# USB_RS485_Conv.net
KiCad netlist of a schematic drawn in EAGLE
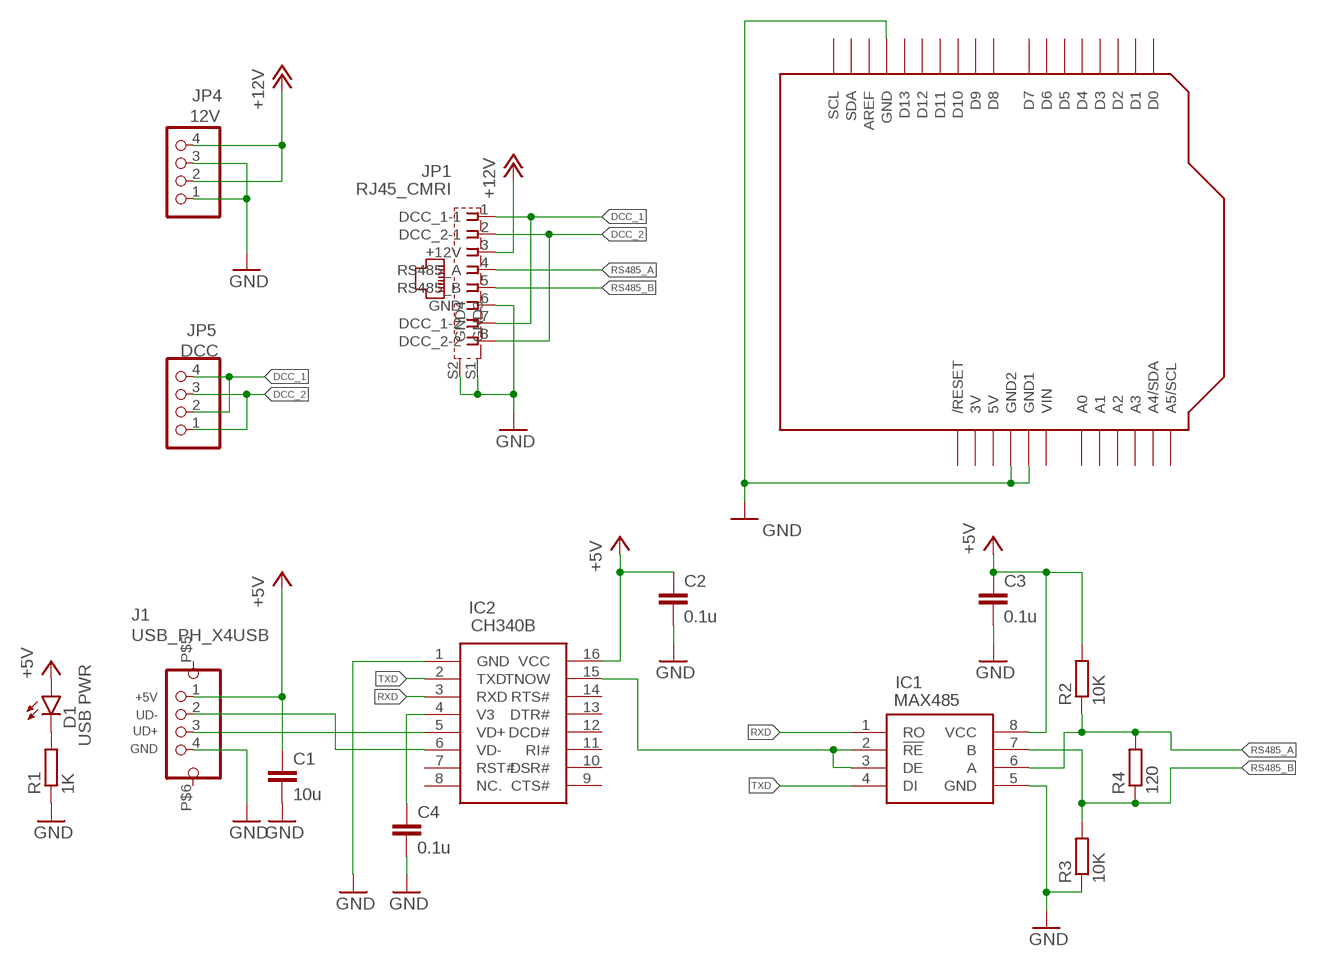
[diagram p0: schematic, sheet 1]

(export (version "E")
  (design (tool "Eeschema 10.0.6"))
  (components
    (comp (ref "C1")
      (value "10u")
      (footprint "eagle-import:C1206")
      (libsource (lib "eagle-import") (part "C-EUC1206"))
    )
    (comp (ref "C2")
      (value "0.1u")
      (footprint "eagle-import:C1206")
      (libsource (lib "eagle-import") (part "C-EUC1206"))
    )
    (comp (ref "C3")
      (value "0.1u")
      (footprint "eagle-import:C1206")
      (libsource (lib "eagle-import") (part "C-EUC1206"))
    )
    (comp (ref "C4")
      (value "0.1u")
      (footprint "eagle-import:C1206")
      (libsource (lib "eagle-import") (part "C-EUC1206"))
    )
    (comp (ref "D1")
      (value "USB PWR")
      (footprint "eagle-import:LED_SMD_1608")
      (libsource (lib "eagle-import") (part "LEDSMD_1608"))
    )
    (comp (ref "IC1")
      (value "MAX485")
      (footprint "eagle-import:SOIC127P600X175-8N")
      (fields (field (name "MANUFACTURER_PART_NUMBER") "MAX485CSA") (field (name "RS_PART_NUMBER") "0370854"))
      (libsource (lib "eagle-import") (part "MAX485CSA"))
    )
    (comp (ref "IC2")
      (value "CH340B")
      (footprint "eagle-import:SOIC127P600X177-16N")
      (fields (field (name "MANUFACTURER_PART_NUMBER") "ULN2003A-DIP16"))
      (libsource (lib "eagle-import") (part "CH340B"))
    )
    (comp (ref "J1")
      (value "USB_PH_X4USB")
      (footprint "eagle-import:USB_PH_04_90")
      (libsource (lib "eagle-import") (part "USB_PH_X4USB"))
    )
    (comp (ref "JP1")
      (value "RJ45_CMRI")
      (footprint "eagle-import:RJ45_7810")
      (libsource (lib "eagle-import") (part "RJ45_CMRI"))
    )
    (comp (ref "JP4")
      (value "12V")
      (footprint "eagle-import:1X04_90")
      (libsource (lib "eagle-import") (part "PINHD-1X4/90"))
    )
    (comp (ref "JP5")
      (value "DCC")
      (footprint "eagle-import:1X04_90")
      (libsource (lib "eagle-import") (part "PINHD-1X4/90"))
    )
    (comp (ref "Q1")
      (value "ARDUINO-SHIELD-NOTEXT")
      (footprint "eagle-import:ARDUINO-SHIELD")
      (libsource (lib "eagle-import") (part "ARDUINO-SHIELD-NOTEXT"))
    )
    (comp (ref "R1")
      (value "1K")
      (footprint "eagle-import:R1206")
      (libsource (lib "eagle-import") (part "R-EU_R1206"))
    )
    (comp (ref "R2")
      (value "10K")
      (footprint "eagle-import:R1206")
      (libsource (lib "eagle-import") (part "R-EU_R1206"))
    )
    (comp (ref "R3")
      (value "10K")
      (footprint "eagle-import:R1206")
      (libsource (lib "eagle-import") (part "R-EU_R1206"))
    )
    (comp (ref "R4")
      (value "120")
      (footprint "eagle-import:R1206")
      (libsource (lib "eagle-import") (part "R-EU_R1206"))
    )
  )
  (nets
    (net (code "1") (name "+5V") (class "Default")
      (node (ref "C1") (pin "1") (pinfunction "1_1") (pintype "passive"))
      (node (ref "C2") (pin "1") (pinfunction "1_1") (pintype "passive"))
      (node (ref "C3") (pin "1") (pinfunction "1_1") (pintype "passive"))
      (node (ref "D1") (pin "A") (pinfunction "A_A") (pintype "passive"))
      (node (ref "IC1") (pin "8") (pinfunction "VCC_8") (pintype "bidirectional"))
      (node (ref "IC2") (pin "16") (pinfunction "VCC_16") (pintype "bidirectional"))
      (node (ref "J1") (pin "1") (pinfunction "1_1") (pintype "passive"))
      (node (ref "R2") (pin "2") (pinfunction "2_2") (pintype "passive"))
    )
    (net (code "2") (name "+12V") (class "Default")
      (node (ref "JP1") (pin "3") (pinfunction "+12V_3") (pintype "power_in"))
      (node (ref "JP4") (pin "2") (pinfunction "2_2") (pintype "passive"))
      (node (ref "JP4") (pin "4") (pinfunction "4_4") (pintype "passive"))
    )
    (net (code "3") (name "DCC_1") (class "Default")
      (node (ref "JP1") (pin "1") (pinfunction "DCC_1-1_1") (pintype "passive"))
      (node (ref "JP1") (pin "7") (pinfunction "DCC_1-2_7") (pintype "passive"))
      (node (ref "JP5") (pin "2") (pinfunction "2_2") (pintype "passive"))
      (node (ref "JP5") (pin "4") (pinfunction "4_4") (pintype "passive"))
    )
    (net (code "4") (name "DCC_2") (class "Default")
      (node (ref "JP1") (pin "2") (pinfunction "DCC_2-1_2") (pintype "passive"))
      (node (ref "JP1") (pin "8") (pinfunction "DCC_2-2_8") (pintype "passive"))
      (node (ref "JP5") (pin "1") (pinfunction "1_1") (pintype "passive"))
      (node (ref "JP5") (pin "3") (pinfunction "3_3") (pintype "passive"))
    )
    (net (code "5") (name "GND") (class "Default")
      (node (ref "C1") (pin "2") (pinfunction "2_2") (pintype "passive"))
      (node (ref "C2") (pin "2") (pinfunction "2_2") (pintype "passive"))
      (node (ref "C3") (pin "2") (pinfunction "2_2") (pintype "passive"))
      (node (ref "C4") (pin "2") (pinfunction "2_2") (pintype "passive"))
      (node (ref "IC1") (pin "5") (pinfunction "GND_5") (pintype "bidirectional"))
      (node (ref "IC2") (pin "1") (pinfunction "GND_1") (pintype "bidirectional"))
      (node (ref "J1") (pin "4") (pinfunction "4_4") (pintype "passive"))
      (node (ref "JP1") (pin "6") (pinfunction "GND_6") (pintype "power_in"))
      (node (ref "JP1") (pin "S1") (pinfunction "GND3_S1") (pintype "passive"))
      (node (ref "JP1") (pin "S2") (pinfunction "GND4_S2") (pintype "passive"))
      (node (ref "JP4") (pin "1") (pinfunction "1_1") (pintype "passive"))
      (node (ref "JP4") (pin "3") (pinfunction "3_3") (pintype "passive"))
      (node (ref "Q1") (pin "GND") (pinfunction "GND_GND") (pintype "bidirectional"))
      (node (ref "Q1") (pin "GND1") (pinfunction "GND1_GND1") (pintype "bidirectional"))
      (node (ref "Q1") (pin "GND2") (pinfunction "GND2_GND2") (pintype "bidirectional"))
      (node (ref "R1") (pin "1") (pinfunction "1_1") (pintype "passive"))
      (node (ref "R3") (pin "1") (pinfunction "1_1") (pintype "passive"))
    )
    (net (code "6") (name "Net-(D1-K)") (class "Default")
      (node (ref "D1") (pin "C") (pinfunction "K_C") (pintype "passive"))
      (node (ref "R1") (pin "2") (pinfunction "2_2") (pintype "passive"))
    )
    (net (code "7") (name "Net-(IC1-DE)") (class "Default")
      (node (ref "IC1") (pin "2") (pinfunction "~{RE}_2") (pintype "bidirectional"))
      (node (ref "IC1") (pin "3") (pinfunction "DE_3") (pintype "bidirectional"))
      (node (ref "IC2") (pin "15") (pinfunction "TNOW_15") (pintype "bidirectional"))
    )
    (net (code "8") (name "Net-(IC2-V3)") (class "Default")
      (node (ref "C4") (pin "1") (pinfunction "1_1") (pintype "passive"))
      (node (ref "IC2") (pin "4") (pinfunction "V3_4") (pintype "bidirectional"))
    )
    (net (code "9") (name "Net-(IC2-VD+)") (class "Default")
      (node (ref "IC2") (pin "5") (pinfunction "VD+_5") (pintype "bidirectional"))
      (node (ref "J1") (pin "3") (pinfunction "3_3") (pintype "passive"))
    )
    (net (code "10") (name "Net-(IC2-VD-)") (class "Default")
      (node (ref "IC2") (pin "6") (pinfunction "VD-_6") (pintype "bidirectional"))
      (node (ref "J1") (pin "2") (pinfunction "2_2") (pintype "passive"))
    )
    (net (code "11") (name "RS485_A") (class "Default")
      (node (ref "IC1") (pin "6") (pinfunction "A_6") (pintype "bidirectional"))
      (node (ref "JP1") (pin "4") (pinfunction "RS485_A_4") (pintype "passive"))
      (node (ref "R2") (pin "1") (pinfunction "1_1") (pintype "passive"))
      (node (ref "R4") (pin "2") (pinfunction "2_2") (pintype "passive"))
    )
    (net (code "12") (name "RS485_B") (class "Default")
      (node (ref "IC1") (pin "7") (pinfunction "B_7") (pintype "bidirectional"))
      (node (ref "JP1") (pin "5") (pinfunction "RS485_B_5") (pintype "passive"))
      (node (ref "R3") (pin "2") (pinfunction "2_2") (pintype "passive"))
      (node (ref "R4") (pin "1") (pinfunction "1_1") (pintype "passive"))
    )
    (net (code "13") (name "RXD") (class "Default")
      (node (ref "IC1") (pin "1") (pinfunction "RO_1") (pintype "bidirectional"))
      (node (ref "IC2") (pin "3") (pinfunction "RXD_3") (pintype "bidirectional"))
    )
    (net (code "14") (name "TXD") (class "Default")
      (node (ref "IC1") (pin "4") (pinfunction "DI_4") (pintype "bidirectional"))
      (node (ref "IC2") (pin "2") (pinfunction "TXD_2") (pintype "bidirectional"))
    )
    (net (code "15") (name "unconnected-(IC2-CTS#-Pad9)") (class "Default")
      (node (ref "IC2") (pin "9") (pinfunction "CTS#_9") (pintype "bidirectional"))
    )
    (net (code "16") (name "unconnected-(IC2-DCD#-Pad12)") (class "Default")
      (node (ref "IC2") (pin "12") (pinfunction "DCD#_12") (pintype "bidirectional"))
    )
    (net (code "17") (name "unconnected-(IC2-DSR#-Pad10)") (class "Default")
      (node (ref "IC2") (pin "10") (pinfunction "DSR#_10") (pintype "bidirectional"))
    )
    (net (code "18") (name "unconnected-(IC2-DTR#-Pad13)") (class "Default")
      (node (ref "IC2") (pin "13") (pinfunction "DTR#_13") (pintype "bidirectional"))
    )
    (net (code "19") (name "unconnected-(IC2-NC.-Pad8)") (class "Default")
      (node (ref "IC2") (pin "8") (pinfunction "NC._8") (pintype "bidirectional"))
    )
    (net (code "20") (name "unconnected-(IC2-RI#-Pad11)") (class "Default")
      (node (ref "IC2") (pin "11") (pinfunction "RI#_11") (pintype "bidirectional"))
    )
    (net (code "21") (name "unconnected-(IC2-RST#-Pad7)") (class "Default")
      (node (ref "IC2") (pin "7") (pinfunction "RST#_7") (pintype "bidirectional"))
    )
    (net (code "22") (name "unconnected-(IC2-RTS#-Pad14)") (class "Default")
      (node (ref "IC2") (pin "14") (pinfunction "RTS#_14") (pintype "bidirectional"))
    )
    (net (code "23") (name "unconnected-(J1-5-PadP$5)") (class "Default")
      (node (ref "J1") (pin "P$5") (pinfunction "5_P$5") (pintype "no_connect"))
    )
    (net (code "24") (name "unconnected-(J1-6-PadP$6)") (class "Default")
      (node (ref "J1") (pin "P$6") (pinfunction "6_P$6") (pintype "no_connect"))
    )
    (net (code "25") (name "unconnected-(Q1-A4{slash}SDA-PadA4)") (class "Default")
      (node (ref "Q1") (pin "A4") (pinfunction "A4/SDA_A4") (pintype "bidirectional"))
    )
    (net (code "26") (name "unconnected-(Q1-A5{slash}SCL-PadA5)") (class "Default")
      (node (ref "Q1") (pin "A5") (pinfunction "A5/SCL_A5") (pintype "bidirectional"))
    )
    (net (code "27") (name "unconnected-(Q1-Pad3V)") (class "Default")
      (node (ref "Q1") (pin "3V") (pinfunction "3V_3V") (pintype "bidirectional"))
    )
    (net (code "28") (name "unconnected-(Q1-Pad5V)") (class "Default")
      (node (ref "Q1") (pin "5V") (pinfunction "5V_5V") (pintype "bidirectional"))
    )
    (net (code "29") (name "unconnected-(Q1-PadA0)") (class "Default")
      (node (ref "Q1") (pin "A0") (pinfunction "A0_A0") (pintype "bidirectional"))
    )
    (net (code "30") (name "unconnected-(Q1-PadA1)") (class "Default")
      (node (ref "Q1") (pin "A1") (pinfunction "A1_A1") (pintype "bidirectional"))
    )
    (net (code "31") (name "unconnected-(Q1-PadA2)") (class "Default")
      (node (ref "Q1") (pin "A2") (pinfunction "A2_A2") (pintype "bidirectional"))
    )
    (net (code "32") (name "unconnected-(Q1-PadA3)") (class "Default")
      (node (ref "Q1") (pin "A3") (pinfunction "A3_A3") (pintype "bidirectional"))
    )
    (net (code "33") (name "unconnected-(Q1-PadAREF)") (class "Default")
      (node (ref "Q1") (pin "AREF") (pinfunction "AREF_AREF") (pintype "bidirectional"))
    )
    (net (code "34") (name "unconnected-(Q1-PadD0)") (class "Default")
      (node (ref "Q1") (pin "D0") (pinfunction "D0_D0") (pintype "bidirectional"))
    )
    (net (code "35") (name "unconnected-(Q1-PadD1)") (class "Default")
      (node (ref "Q1") (pin "D1") (pinfunction "D1_D1") (pintype "bidirectional"))
    )
    (net (code "36") (name "unconnected-(Q1-PadD2)") (class "Default")
      (node (ref "Q1") (pin "D2") (pinfunction "D2_D2") (pintype "bidirectional"))
    )
    (net (code "37") (name "unconnected-(Q1-PadD3)") (class "Default")
      (node (ref "Q1") (pin "D3") (pinfunction "D3_D3") (pintype "bidirectional"))
    )
    (net (code "38") (name "unconnected-(Q1-PadD4)") (class "Default")
      (node (ref "Q1") (pin "D4") (pinfunction "D4_D4") (pintype "bidirectional"))
    )
    (net (code "39") (name "unconnected-(Q1-PadD5)") (class "Default")
      (node (ref "Q1") (pin "D5") (pinfunction "D5_D5") (pintype "bidirectional"))
    )
    (net (code "40") (name "unconnected-(Q1-PadD6)") (class "Default")
      (node (ref "Q1") (pin "D6") (pinfunction "D6_D6") (pintype "bidirectional"))
    )
    (net (code "41") (name "unconnected-(Q1-PadD7)") (class "Default")
      (node (ref "Q1") (pin "D7") (pinfunction "D7_D7") (pintype "bidirectional"))
    )
    (net (code "42") (name "unconnected-(Q1-PadD8)") (class "Default")
      (node (ref "Q1") (pin "D8") (pinfunction "D8_D8") (pintype "bidirectional"))
    )
    (net (code "43") (name "unconnected-(Q1-PadD9)") (class "Default")
      (node (ref "Q1") (pin "D9") (pinfunction "D9_D9") (pintype "bidirectional"))
    )
    (net (code "44") (name "unconnected-(Q1-PadD10)") (class "Default")
      (node (ref "Q1") (pin "D10") (pinfunction "D10_D10") (pintype "bidirectional"))
    )
    (net (code "45") (name "unconnected-(Q1-PadD11)") (class "Default")
      (node (ref "Q1") (pin "D11") (pinfunction "D11_D11") (pintype "bidirectional"))
    )
    (net (code "46") (name "unconnected-(Q1-PadD12)") (class "Default")
      (node (ref "Q1") (pin "D12") (pinfunction "D12_D12") (pintype "bidirectional"))
    )
    (net (code "47") (name "unconnected-(Q1-PadD13)") (class "Default")
      (node (ref "Q1") (pin "D13") (pinfunction "D13_D13") (pintype "bidirectional"))
    )
    (net (code "48") (name "unconnected-(Q1-PadSCL)") (class "Default")
      (node (ref "Q1") (pin "SCL") (pinfunction "SCL_SCL") (pintype "bidirectional"))
    )
    (net (code "49") (name "unconnected-(Q1-PadSDA)") (class "Default")
      (node (ref "Q1") (pin "SDA") (pinfunction "SDA_SDA") (pintype "bidirectional"))
    )
    (net (code "50") (name "unconnected-(Q1-PadVIN)") (class "Default")
      (node (ref "Q1") (pin "VIN") (pinfunction "VIN_VIN") (pintype "bidirectional"))
    )
    (net (code "51") (name "unconnected-(Q1-{slash}RESET-PadRESET)") (class "Default")
      (node (ref "Q1") (pin "RESET") (pinfunction "/RESET_RESET") (pintype "bidirectional"))
    )
  )
)
